# pi_breakout.net
KiCad netlist of a schematic drawn in Altium Designer
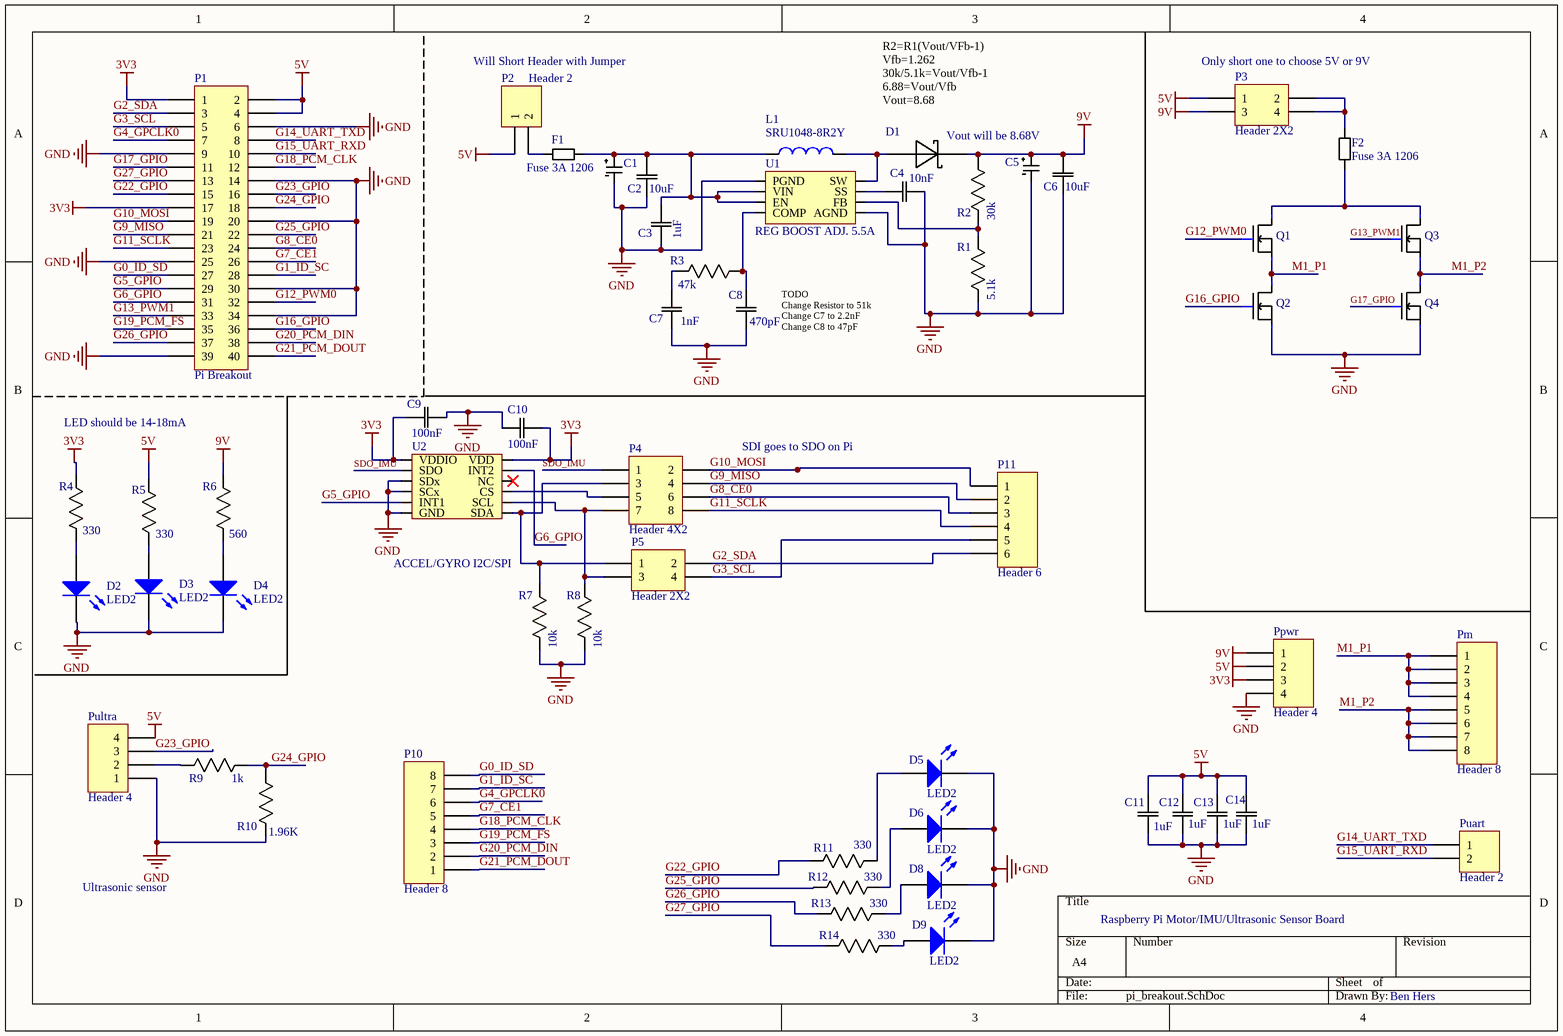
[diagram p0: pi_breakout.SchDoc]

(export (version "E")
  (design (tool "Eeschema 10.0.6"))
  (components
    (comp (ref "C1")
      (value "CAP ALUM 470UF RADIAL")
      (footprint "Aluminum Electrolytic Capacitors Radial")
      (description "470µF 35V Aluminum Electrolytic Capacitors Radial, Can - SMD  5000 Hrs @ 105°C")
      (fields (field (name "MF") "Panasonic Electronic Components") (field (name "MP") "EEV-FK1V471Q"))
      (libsource (lib "AltiumLibraries") (part "CAP ALUM 470UF Aluminum Electrolytic Radial"))
    )
    (comp (ref "C2")
      (value "10uF")
      (footprint "0805")
      (description "CAP CER 10UF 10V X5R 0805")
      (fields (field (name "MP") "C0805C106K8PACTU") (field (name "MF") "KEMET"))
      (libsource (lib "") (part "CAP 10uF 0805_1"))
    )
    (comp (ref "C3")
      (value "1uF")
      (footprint "0805")
      (description "CAP CER 1UF 50V X7R 0805")
      (fields (field (name "MP") "CL21B105KBFNNNE") (field (name "MF") "Samsung Electro-Mechanics"))
      (libsource (lib "") (part "CAP 1uF 0805_1"))
    )
    (comp (ref "C4")
      (value "10nF")
      (footprint "0805")
      (description "CAP CER 10000PF 50V X7R 0805")
      (fields (field (name "MP") "CC0805KRX7R9BB103") (field (name "MF") "Yageo"))
      (libsource (lib "AltiumLibraries") (part "CAP 10nF 0805"))
    )
    (comp (ref "C5")
      (value "CAP ALUM 470UF RADIAL")
      (footprint "Aluminum Electrolytic Capacitors Radial")
      (description "470µF 35V Aluminum Electrolytic Capacitors Radial, Can - SMD  5000 Hrs @ 105°C")
      (fields (field (name "MF") "Panasonic Electronic Components") (field (name "MP") "EEV-FK1V471Q"))
      (libsource (lib "AltiumLibraries") (part "CAP ALUM 470UF Aluminum Electrolytic Radial"))
    )
    (comp (ref "C6")
      (value "10uF")
      (footprint "0805")
      (description "CAP CER 10UF 10V X5R 0805")
      (fields (field (name "MP") "C0805C106K8PACTU") (field (name "MF") "KEMET"))
      (libsource (lib "AltiumLibraries") (part "CAP 10uF 0805"))
    )
    (comp (ref "C7")
      (value "1nF")
      (footprint "0805")
      (description "CAP CER 1000PF 50V X7R 0805")
      (fields (field (name "MP") "CC0805KRX7R9BB102") (field (name "MF") "Yageo"))
      (libsource (lib "AltiumLibraries") (part "CAP 1nF 0805"))
    )
    (comp (ref "C8")
      (value "470pF")
      (footprint "0805")
      (description "CAP CER 470PF 50V C0G/NPO 0805")
      (fields (field (name "MP") "CC0805JRNPO9BN471") (field (name "MF") "Yageo"))
      (libsource (lib "AltiumLibraries") (part "CAP 470pF 0805"))
    )
    (comp (ref "C9")
      (value "100nF")
      (footprint "0805")
      (description "CAP CER 0.1UF 50V X7R 0805")
      (fields (field (name "MP") "CC0805KRX7R9BB104") (field (name "MF") "Yageo"))
      (libsource (lib "AltiumLibraries") (part "CAP 100nF 0805"))
    )
    (comp (ref "C10")
      (value "100nF")
      (footprint "0805")
      (description "CAP CER 0.1UF 50V X7R 0805")
      (fields (field (name "MP") "CC0805KRX7R9BB104") (field (name "MF") "Yageo"))
      (libsource (lib "AltiumLibraries") (part "CAP 100nF 0805"))
    )
    (comp (ref "C11")
      (value "1uF")
      (footprint "0805")
      (description "CAP CER 1UF 50V X7R 0805")
      (fields (field (name "MP") "CL21B105KBFNNNE") (field (name "MF") "Samsung Electro-Mechanics"))
      (libsource (lib "AltiumLibraries") (part "CAP 1uF 0805"))
    )
    (comp (ref "C12")
      (value "1uF")
      (footprint "0805")
      (description "CAP CER 1UF 50V X7R 0805")
      (fields (field (name "MP") "CL21B105KBFNNNE") (field (name "MF") "Samsung Electro-Mechanics"))
      (libsource (lib "AltiumLibraries") (part "CAP 1uF 0805"))
    )
    (comp (ref "C13")
      (value "1uF")
      (footprint "0805")
      (description "CAP CER 1UF 50V X7R 0805")
      (fields (field (name "MP") "CL21B105KBFNNNE") (field (name "MF") "Samsung Electro-Mechanics"))
      (libsource (lib "AltiumLibraries") (part "CAP 1uF 0805"))
    )
    (comp (ref "C14")
      (value "1uF")
      (footprint "0805")
      (description "CAP CER 1UF 50V X7R 0805")
      (fields (field (name "MP") "CL21B105KBFNNNE") (field (name "MF") "Samsung Electro-Mechanics"))
      (libsource (lib "AltiumLibraries") (part "CAP 1uF 0805"))
    )
    (comp (ref "D1")
      (value "DIODE SCHOTTKY 40V 3A SMC")
      (footprint "SMC")
      (description "Diode Schottky 40V 3A Surface Mount SMC")
      (fields (field (name "MF") "Diodes Incorporated") (field (name "MP") "B340-13-F"))
      (libsource (lib "AltiumLibraries") (part "B340-13-F"))
    )
    (comp (ref "D2")
      (value "LED2")
      (footprint "3.2X1.6X1.1")
      (description "Typical RED, GREEN, YELLOW, AMBER GaAs LED")
      (fields (field (name "MF") "Lite-On Inc.") (field (name "MP") "LTST-C191KGKT"))
      (libsource (lib "AltiumLibraries") (part "LED GREEN SMD"))
    )
    (comp (ref "D3")
      (value "LED2")
      (footprint "3.2X1.6X1.1")
      (description "Typical RED, GREEN, YELLOW, AMBER GaAs LED")
      (fields (field (name "MF") "Lite-On Inc.") (field (name "MP") "LTST-C191KGKT"))
      (libsource (lib "AltiumLibraries") (part "LED GREEN SMD"))
    )
    (comp (ref "D4")
      (value "LED2")
      (footprint "3.2X1.6X1.1")
      (description "Typical RED, GREEN, YELLOW, AMBER GaAs LED")
      (fields (field (name "MF") "Lite-On Inc.") (field (name "MP") "LTST-C191KGKT"))
      (libsource (lib "AltiumLibraries") (part "LED GREEN SMD"))
    )
    (comp (ref "D5")
      (value "LED2")
      (footprint "3.2X1.6X1.1")
      (description "Typical RED, GREEN, YELLOW, AMBER GaAs LED")
      (fields (field (name "MF") "Lite-On Inc.") (field (name "MP") "LTST-C191KGKT"))
      (libsource (lib "AltiumLibraries") (part "LED GREEN SMD"))
    )
    (comp (ref "D6")
      (value "LED2")
      (footprint "3.2X1.6X1.1")
      (description "Typical RED, GREEN, YELLOW, AMBER GaAs LED")
      (fields (field (name "MF") "Lite-On Inc.") (field (name "MP") "LTST-C191KGKT"))
      (libsource (lib "AltiumLibraries") (part "LED GREEN SMD"))
    )
    (comp (ref "D8")
      (value "LED2")
      (footprint "3.2X1.6X1.1")
      (description "Typical RED, GREEN, YELLOW, AMBER GaAs LED")
      (fields (field (name "MF") "Lite-On Inc.") (field (name "MP") "LTST-C191KGKT"))
      (libsource (lib "AltiumLibraries") (part "LED GREEN SMD"))
    )
    (comp (ref "D9")
      (value "LED2")
      (footprint "3.2X1.6X1.1")
      (description "Typical RED, GREEN, YELLOW, AMBER GaAs LED")
      (fields (field (name "MF") "Lite-On Inc.") (field (name "MP") "LTST-C191KGKT"))
      (libsource (lib "AltiumLibraries") (part "LED GREEN SMD"))
    )
    (comp (ref "F1")
      (value "Fuse 3A 1206")
      (footprint "1206")
      (description "FUSE 3.0A 63VAC/DC SLOW 1206")
      (fields (field (name "MF") "Bel Fuse Inc.") (field (name "MP") "0685T3000-01"))
      (libsource (lib "AltiumLibraries") (part "Fuse 3A 1206"))
    )
    (comp (ref "F2")
      (value "Fuse 3A 1206")
      (footprint "1206")
      (description "FUSE 3.0A 63VAC/DC SLOW 1206")
      (fields (field (name "MF") "Bel Fuse Inc.") (field (name "MP") "0685T3000-01"))
      (libsource (lib "AltiumLibraries") (part "Fuse 3A 1206"))
    )
    (comp (ref "L1")
      (value "SRU1048-8R2Y")
      (footprint "Inductor")
      (description "FIXED IND 8.2UH 4.6A 15 MOHM SMD")
      (fields (field (name "MF") "Bourns Inc."))
      (libsource (lib "AltiumLibraries") (part "SRU1048-8R2Y"))
    )
    (comp (ref "P1")
      (value "Pi Breakout")
      (footprint "HDR2X20")
      (description "Header, 20-Pin, Dual row")
      (fields (field (name "PUBLISHER") "Altium Limited"))
      (libsource (lib "Miscellaneous Connectors") (part "Header 20X2"))
    )
    (comp (ref "P2")
      (value "Header 2")
      (footprint "HDR1X2")
      (description "Header, 2-Pin")
      (fields (field (name "PUBLISHER") "Altium Limited"))
      (libsource (lib "Miscellaneous Connectors") (part "Header 2"))
    )
    (comp (ref "P3")
      (value "Header 2X2")
      (footprint "HDR2X2")
      (description "Header, 2-Pin, Dual row")
      (fields (field (name "PUBLISHER") "Altium Limited"))
      (libsource (lib "Miscellaneous Connectors") (part "Header 2X2"))
    )
    (comp (ref "P4")
      (value "Header 4X2")
      (footprint "HDR2X4")
      (description "Header, 4-Pin, Dual row")
      (fields (field (name "PUBLISHER") "Altium Limited"))
      (libsource (lib "Miscellaneous Connectors") (part "Header 4X2"))
    )
    (comp (ref "P5")
      (value "Header 2X2")
      (footprint "HDR2X2")
      (description "Header, 2-Pin, Dual row")
      (fields (field (name "PUBLISHER") "Altium Limited"))
      (libsource (lib "Miscellaneous Connectors") (part "Header 2X2"))
    )
    (comp (ref "P10")
      (value "Header 8")
      (footprint "HDR1X8")
      (description "Header, 8-Pin")
      (fields (field (name "PUBLISHER") "Altium Limited"))
      (libsource (lib "Miscellaneous Connectors") (part "Header 8"))
    )
    (comp (ref "P11")
      (value "Header 6")
      (footprint "HDR1X6")
      (description "Header, 6-Pin")
      (fields (field (name "PUBLISHER") "Altium Limited"))
      (libsource (lib "Miscellaneous Connectors") (part "Header 6"))
    )
    (comp (ref "Pm")
      (value "Header 8")
      (footprint "HDR1X8")
      (description "Header, 8-Pin")
      (fields (field (name "PUBLISHER") "Altium Limited"))
      (libsource (lib "") (part "Header 8_1"))
    )
    (comp (ref "Ppwr")
      (value "Header 4")
      (footprint "HDR1X4")
      (description "Header, 4-Pin")
      (fields (field (name "PUBLISHER") "Altium Limited"))
      (libsource (lib "") (part "Header 4_1"))
    )
    (comp (ref "Puart")
      (value "Header 2")
      (footprint "HDR1X2")
      (description "Header, 2-Pin")
      (fields (field (name "PUBLISHER") "Altium Limited"))
      (libsource (lib "") (part "Header 2_1"))
    )
    (comp (ref "Pultra")
      (value "Header 4")
      (footprint "HDR1X4")
      (description "Header, 4-Pin")
      (fields (field (name "PUBLISHER") "Altium Limited"))
      (libsource (lib "Miscellaneous Connectors") (part "Header 4"))
    )
    (comp (ref "Q1")
      (value "N-Channel")
      (footprint "8-SOIC MOSFET")
      (description "MOSFET N-CH 30V 18.5A 8-SOIC")
      (fields (field (name "MF") "ON Semiconductor") (field (name "MP") "FDS8813NZ"))
      (libsource (lib "AltiumLibraries") (part "MOSFET N Channel 8-SOIC"))
    )
    (comp (ref "Q2")
      (value "N-Channel")
      (footprint "8-SOIC MOSFET")
      (description "MOSFET N-CH 30V 18.5A 8-SOIC")
      (fields (field (name "MF") "ON Semiconductor") (field (name "MP") "FDS8813NZ"))
      (libsource (lib "AltiumLibraries") (part "MOSFET N Channel 8-SOIC"))
    )
    (comp (ref "Q3")
      (value "N-Channel")
      (footprint "8-SOIC MOSFET")
      (description "MOSFET N-CH 30V 18.5A 8-SOIC")
      (fields (field (name "MF") "ON Semiconductor") (field (name "MP") "FDS8813NZ"))
      (libsource (lib "AltiumLibraries") (part "MOSFET N Channel 8-SOIC"))
    )
    (comp (ref "Q4")
      (value "N-Channel")
      (footprint "8-SOIC MOSFET")
      (description "MOSFET N-CH 30V 18.5A 8-SOIC")
      (fields (field (name "MF") "ON Semiconductor") (field (name "MP") "FDS8813NZ"))
      (libsource (lib "AltiumLibraries") (part "MOSFET N Channel 8-SOIC"))
    )
    (comp (ref "R1")
      (value "5.1k")
      (footprint "0805")
      (description "RES SMD 5.1K OHM 1% 1/8W 0805")
      (fields (field (name "MP") "RC0805FR-075K1L") (field (name "MF") "Yageo"))
      (libsource (lib "AltiumLibraries") (part "RES 5.1k 0805"))
    )
    (comp (ref "R2")
      (value "30k")
      (footprint "0805")
      (description "RES SMD 30K OHM 1% 1/8W 0805")
      (fields (field (name "MP") "RC0805FR-0730KL") (field (name "MF") "Yageo"))
      (libsource (lib "AltiumLibraries") (part "RES 30k 0805"))
    )
    (comp (ref "R3")
      (value "47k")
      (footprint "0805")
      (description "RES SMD 47K OHM 1% 1/8W 0805")
      (fields (field (name "MP") "RC0805FR-0747KL") (field (name "MF") "Yageo"))
      (libsource (lib "AltiumLibraries") (part "RES 47k 0805"))
    )
    (comp (ref "R4")
      (value "330")
      (footprint "0805")
      (description "RES SMD 330 OHM 1% 1/8W 0805")
      (fields (field (name "MP") "RC0805FR-07330RL") (field (name "MF") "Yageo"))
      (libsource (lib "AltiumLibraries") (part "RES 330 0805"))
    )
    (comp (ref "R5")
      (value "330")
      (footprint "0805")
      (description "RES SMD 330 OHM 1% 1/8W 0805")
      (fields (field (name "MP") "RC0805FR-07330RL") (field (name "MF") "Yageo"))
      (libsource (lib "AltiumLibraries") (part "RES 330 0805"))
    )
    (comp (ref "R6")
      (value "560")
      (footprint "0805")
      (description "RES 560 OHM 1% 1/8W 0805")
      (fields (field (name "MP") "RMCF0805FT560R") (field (name "MF") "Stackpole Electronics Inc"))
      (libsource (lib "AltiumLibraries") (part "RES 560 0805"))
    )
    (comp (ref "R7")
      (value "10k")
      (footprint "0805")
      (description "RES SMD 10K OHM 1% 1/8W 0805")
      (fields (field (name "MP") "RC0805FR-0710KL") (field (name "MF") "Yageo"))
      (libsource (lib "AltiumLibraries") (part "RES 10k 0805"))
    )
    (comp (ref "R8")
      (value "10k")
      (footprint "0805")
      (description "RES SMD 10K OHM 1% 1/8W 0805")
      (fields (field (name "MP") "RC0805FR-0710KL") (field (name "MF") "Yageo"))
      (libsource (lib "AltiumLibraries") (part "RES 10k 0805"))
    )
    (comp (ref "R9")
      (value "1k")
      (footprint "0805")
      (description "RES SMD 1K OHM 5% 1/8W 0805")
      (fields (field (name "MP") "RC0805JR-071KL") (field (name "MF") "Yageo"))
      (libsource (lib "AltiumLibraries") (part "RES 1k 0805"))
    )
    (comp (ref "R10")
      (value "1.96K")
      (footprint "0805")
      (description "RES SMD 1.96K OHM 1% 1/8W 0805")
      (fields (field (name "MP") "ERJ-6ENF1961V") (field (name "MF") "Panasonic Electronic Components"))
      (libsource (lib "AltiumLibraries") (part "RES 1.96k 0805"))
    )
    (comp (ref "R11")
      (value "330")
      (footprint "0805")
      (description "RES SMD 330 OHM 1% 1/8W 0805")
      (fields (field (name "MP") "RC0805FR-07330RL") (field (name "MF") "Yageo"))
      (libsource (lib "AltiumLibraries") (part "RES 330 0805"))
    )
    (comp (ref "R12")
      (value "330")
      (footprint "0805")
      (description "RES SMD 330 OHM 1% 1/8W 0805")
      (fields (field (name "MP") "RC0805FR-07330RL") (field (name "MF") "Yageo"))
      (libsource (lib "AltiumLibraries") (part "RES 330 0805"))
    )
    (comp (ref "R13")
      (value "330")
      (footprint "0805")
      (description "RES SMD 330 OHM 1% 1/8W 0805")
      (fields (field (name "MP") "RC0805FR-07330RL") (field (name "MF") "Yageo"))
      (libsource (lib "AltiumLibraries") (part "RES 330 0805"))
    )
    (comp (ref "R14")
      (value "330")
      (footprint "0805")
      (description "RES SMD 330 OHM 1% 1/8W 0805")
      (fields (field (name "MP") "RC0805FR-07330RL") (field (name "MF") "Yageo"))
      (libsource (lib "AltiumLibraries") (part "RES 330 0805"))
    )
    (comp (ref "U1")
      (value "REG BOOST ADJ. 5.5A")
      (footprint "ICREGBOOSTADJUSTABLE5.5A8SO")
      (fields (field (name "MF") "Diodes Incorporated") (field (name "MP") "PAM2423AECADJR"))
      (libsource (lib "AltiumLibraries") (part "REG BOOST ADJUSTABLE 5.5A 8SO"))
    )
    (comp (ref "U2")
      (value "ACCEL/GYRO I2C/SPI")
      (footprint "IMU 14-LGA")
      (description "Accelerometer, Gyroscope, Temperature, 6 Axis Sensor I²C, SPI Output")
      (fields (field (name "MP") "LSM6DSLTR") (field (name "MF") "STMicroelectronics"))
      (libsource (lib "AltiumLibraries") (part "IMU 14LGA"))
    )
  )
  (nets
    (net (code "1") (name "/G0_ID_SD") (class "Default")
      (node (ref "P1") (pin "27") (pinfunction "27_27") (pintype "passive"))
      (node (ref "P10") (pin "8") (pinfunction "8_8") (pintype "passive"))
    )
    (net (code "2") (name "/G1_ID_SC") (class "Default")
      (node (ref "P1") (pin "28") (pinfunction "28_28") (pintype "passive"))
      (node (ref "P10") (pin "7") (pinfunction "7_7") (pintype "passive"))
    )
    (net (code "3") (name "/G2_SDA") (class "Default")
      (node (ref "P1") (pin "3") (pinfunction "3_3") (pintype "passive"))
      (node (ref "P11") (pin "6") (pinfunction "6_6") (pintype "passive"))
      (node (ref "P5") (pin "2") (pinfunction "2_2") (pintype "passive"))
    )
    (net (code "4") (name "/G3_SCL") (class "Default")
      (node (ref "P1") (pin "5") (pinfunction "5_5") (pintype "passive"))
      (node (ref "P11") (pin "5") (pinfunction "5_5") (pintype "passive"))
      (node (ref "P5") (pin "4") (pinfunction "4_4") (pintype "passive"))
    )
    (net (code "5") (name "/G4_GPCLK0") (class "Default")
      (node (ref "P1") (pin "7") (pinfunction "7_7") (pintype "passive"))
      (node (ref "P10") (pin "6") (pinfunction "6_6") (pintype "passive"))
    )
    (net (code "6") (name "/G5_GPIO") (class "Default")
      (node (ref "P1") (pin "29") (pinfunction "29_29") (pintype "passive"))
      (node (ref "U2") (pin "INT1") (pinfunction "INT1_INT1") (pintype "passive"))
    )
    (net (code "7") (name "/G6_GPIO") (class "Default")
      (node (ref "P1") (pin "31") (pinfunction "31_31") (pintype "passive"))
      (node (ref "U2") (pin "INT2") (pinfunction "INT2_INT2") (pintype "passive"))
    )
    (net (code "8") (name "/G7_CE1") (class "Default")
      (node (ref "P1") (pin "26") (pinfunction "26_26") (pintype "passive"))
      (node (ref "P10") (pin "5") (pinfunction "5_5") (pintype "passive"))
    )
    (net (code "9") (name "/G8_CE0") (class "Default")
      (node (ref "P1") (pin "24") (pinfunction "24_24") (pintype "passive"))
      (node (ref "P11") (pin "3") (pinfunction "3_3") (pintype "passive"))
      (node (ref "P4") (pin "6") (pinfunction "6_6") (pintype "passive"))
    )
    (net (code "10") (name "/G9_MISO") (class "Default")
      (node (ref "P1") (pin "21") (pinfunction "21_21") (pintype "passive"))
      (node (ref "P11") (pin "2") (pinfunction "2_2") (pintype "passive"))
      (node (ref "P4") (pin "4") (pinfunction "4_4") (pintype "passive"))
    )
    (net (code "11") (name "/G10_MOSI") (class "Default")
      (node (ref "P1") (pin "19") (pinfunction "19_19") (pintype "passive"))
      (node (ref "P11") (pin "1") (pinfunction "1_1") (pintype "passive"))
      (node (ref "P4") (pin "2") (pinfunction "2_2") (pintype "passive"))
    )
    (net (code "12") (name "/G11_SCLK") (class "Default")
      (node (ref "P1") (pin "23") (pinfunction "23_23") (pintype "passive"))
      (node (ref "P11") (pin "4") (pinfunction "4_4") (pintype "passive"))
      (node (ref "P4") (pin "8") (pinfunction "8_8") (pintype "passive"))
    )
    (net (code "13") (name "/G12_PWM0") (class "Default")
      (node (ref "P1") (pin "32") (pinfunction "32_32") (pintype "passive"))
      (node (ref "Q1") (pin "G") (pinfunction "G_G") (pintype "passive"))
    )
    (net (code "14") (name "/G13_PWM1") (class "Default")
      (node (ref "P1") (pin "33") (pinfunction "33_33") (pintype "passive"))
      (node (ref "Q3") (pin "G") (pinfunction "G_G") (pintype "passive"))
    )
    (net (code "15") (name "/G14_UART_TXD") (class "Default")
      (node (ref "P1") (pin "8") (pinfunction "8_8") (pintype "passive"))
      (node (ref "Puart") (pin "1") (pinfunction "1_1") (pintype "passive"))
    )
    (net (code "16") (name "/G15_UART_RXD") (class "Default")
      (node (ref "P1") (pin "10") (pinfunction "10_10") (pintype "passive"))
      (node (ref "Puart") (pin "2") (pinfunction "2_2") (pintype "passive"))
    )
    (net (code "17") (name "/G16_GPIO") (class "Default")
      (node (ref "P1") (pin "36") (pinfunction "36_36") (pintype "passive"))
      (node (ref "Q2") (pin "G") (pinfunction "G_G") (pintype "passive"))
    )
    (net (code "18") (name "/G17_GPIO") (class "Default")
      (node (ref "P1") (pin "11") (pinfunction "11_11") (pintype "passive"))
      (node (ref "Q4") (pin "G") (pinfunction "G_G") (pintype "passive"))
    )
    (net (code "19") (name "/G18_PCM_CLK") (class "Default")
      (node (ref "P1") (pin "12") (pinfunction "12_12") (pintype "passive"))
      (node (ref "P10") (pin "4") (pinfunction "4_4") (pintype "passive"))
    )
    (net (code "20") (name "/G19_PCM_FS") (class "Default")
      (node (ref "P1") (pin "35") (pinfunction "35_35") (pintype "passive"))
      (node (ref "P10") (pin "3") (pinfunction "3_3") (pintype "passive"))
    )
    (net (code "21") (name "/G20_PCM_DIN") (class "Default")
      (node (ref "P1") (pin "38") (pinfunction "38_38") (pintype "passive"))
      (node (ref "P10") (pin "2") (pinfunction "2_2") (pintype "passive"))
    )
    (net (code "22") (name "/G21_PCM_DOUT") (class "Default")
      (node (ref "P1") (pin "40") (pinfunction "40_40") (pintype "passive"))
      (node (ref "P10") (pin "1") (pinfunction "1_1") (pintype "passive"))
    )
    (net (code "23") (name "/G22_GPIO") (class "Default")
      (node (ref "P1") (pin "15") (pinfunction "15_15") (pintype "passive"))
      (node (ref "R11") (pin "1") (pinfunction "R1_1") (pintype "passive"))
    )
    (net (code "24") (name "/G23_GPIO") (class "Default")
      (node (ref "P1") (pin "16") (pinfunction "16_16") (pintype "passive"))
      (node (ref "Pultra") (pin "3") (pinfunction "3_3") (pintype "passive"))
    )
    (net (code "25") (name "/G24_GPIO") (class "Default")
      (node (ref "P1") (pin "18") (pinfunction "18_18") (pintype "passive"))
      (node (ref "R10") (pin "1") (pinfunction "R1_1") (pintype "passive"))
      (node (ref "R9") (pin "1") (pinfunction "R1_1") (pintype "passive"))
    )
    (net (code "26") (name "/G25_GPIO") (class "Default")
      (node (ref "P1") (pin "22") (pinfunction "22_22") (pintype "passive"))
      (node (ref "R12") (pin "1") (pinfunction "R1_1") (pintype "passive"))
    )
    (net (code "27") (name "/G26_GPIO") (class "Default")
      (node (ref "P1") (pin "37") (pinfunction "37_37") (pintype "passive"))
      (node (ref "R13") (pin "1") (pinfunction "R1_1") (pintype "passive"))
    )
    (net (code "28") (name "/G27_GPIO") (class "Default")
      (node (ref "P1") (pin "13") (pinfunction "13_13") (pintype "passive"))
      (node (ref "R14") (pin "1") (pinfunction "R1_1") (pintype "passive"))
    )
    (net (code "29") (name "/M1_P1") (class "Default")
      (node (ref "Pm") (pin "1") (pinfunction "1_1") (pintype "passive"))
      (node (ref "Pm") (pin "2") (pinfunction "2_2") (pintype "passive"))
      (node (ref "Pm") (pin "3") (pinfunction "3_3") (pintype "passive"))
      (node (ref "Pm") (pin "4") (pinfunction "4_4") (pintype "passive"))
      (node (ref "Q1") (pin "S") (pinfunction "S_S") (pintype "passive"))
      (node (ref "Q2") (pin "D") (pinfunction "D_D") (pintype "passive"))
    )
    (net (code "30") (name "/M1_P2") (class "Default")
      (node (ref "Pm") (pin "5") (pinfunction "5_5") (pintype "passive"))
      (node (ref "Pm") (pin "6") (pinfunction "6_6") (pintype "passive"))
      (node (ref "Pm") (pin "7") (pinfunction "7_7") (pintype "passive"))
      (node (ref "Pm") (pin "8") (pinfunction "8_8") (pintype "passive"))
      (node (ref "Q3") (pin "S") (pinfunction "S_S") (pintype "passive"))
      (node (ref "Q4") (pin "D") (pinfunction "D_D") (pintype "passive"))
    )
    (net (code "31") (name "/SDO_IMU") (class "Default")
      (node (ref "P4") (pin "1") (pinfunction "1_1") (pintype "passive"))
      (node (ref "U2") (pin "SDO") (pinfunction "SDO_SDO") (pintype "passive"))
    )
    (net (code "32") (name "3V3") (class "Default")
      (node (ref "C10") (pin "2") (pinfunction "C2_2") (pintype "passive"))
      (node (ref "C9") (pin "1") (pinfunction "C1_1") (pintype "passive"))
      (node (ref "P1") (pin "1") (pinfunction "1_1") (pintype "passive"))
      (node (ref "P1") (pin "17") (pinfunction "17_17") (pintype "passive"))
      (node (ref "Ppwr") (pin "3") (pinfunction "3_3") (pintype "passive"))
      (node (ref "R4") (pin "1") (pinfunction "R1_1") (pintype "passive"))
      (node (ref "U2") (pin "VDD") (pinfunction "VDD_VDD") (pintype "passive"))
      (node (ref "U2") (pin "VDDIO") (pinfunction "VDDIO_VDDIO") (pintype "passive"))
    )
    (net (code "33") (name "5V") (class "Default")
      (node (ref "C11") (pin "2") (pinfunction "C2_2") (pintype "passive"))
      (node (ref "C12") (pin "2") (pinfunction "C2_2") (pintype "passive"))
      (node (ref "C13") (pin "2") (pinfunction "C2_2") (pintype "passive"))
      (node (ref "C14") (pin "2") (pinfunction "C2_2") (pintype "passive"))
      (node (ref "P1") (pin "2") (pinfunction "2_2") (pintype "passive"))
      (node (ref "P1") (pin "4") (pinfunction "4_4") (pintype "passive"))
      (node (ref "P2") (pin "1") (pinfunction "1_1") (pintype "passive"))
      (node (ref "P3") (pin "1") (pinfunction "1_1") (pintype "passive"))
      (node (ref "Ppwr") (pin "2") (pinfunction "2_2") (pintype "passive"))
      (node (ref "Pultra") (pin "4") (pinfunction "4_4") (pintype "passive"))
      (node (ref "R5") (pin "1") (pinfunction "R1_1") (pintype "passive"))
    )
    (net (code "34") (name "9V") (class "Default")
      (node (ref "C5") (pin "1") (pinfunction "1_1") (pintype "passive"))
      (node (ref "C6") (pin "2") (pinfunction "C2_2") (pintype "passive"))
      (node (ref "D1") (pin "1") (pinfunction "K_1") (pintype "passive"))
      (node (ref "P3") (pin "3") (pinfunction "3_3") (pintype "passive"))
      (node (ref "Ppwr") (pin "1") (pinfunction "1_1") (pintype "passive"))
      (node (ref "R2") (pin "1") (pinfunction "R1_1") (pintype "passive"))
      (node (ref "R6") (pin "1") (pinfunction "R1_1") (pintype "passive"))
    )
    (net (code "35") (name "GND") (class "Default")
      (node (ref "C1") (pin "2") (pinfunction "2_2") (pintype "passive"))
      (node (ref "C10") (pin "1") (pinfunction "C1_1") (pintype "passive"))
      (node (ref "C11") (pin "1") (pinfunction "C1_1") (pintype "passive"))
      (node (ref "C12") (pin "1") (pinfunction "C1_1") (pintype "passive"))
      (node (ref "C13") (pin "1") (pinfunction "C1_1") (pintype "passive"))
      (node (ref "C14") (pin "1") (pinfunction "C1_1") (pintype "passive"))
      (node (ref "C2") (pin "1") (pinfunction "C1_1") (pintype "passive"))
      (node (ref "C3") (pin "1") (pinfunction "C1_1") (pintype "passive"))
      (node (ref "C4") (pin "2") (pinfunction "C2_2") (pintype "passive"))
      (node (ref "C5") (pin "2") (pinfunction "2_2") (pintype "passive"))
      (node (ref "C6") (pin "1") (pinfunction "C1_1") (pintype "passive"))
      (node (ref "C7") (pin "1") (pinfunction "C1_1") (pintype "passive"))
      (node (ref "C8") (pin "1") (pinfunction "C1_1") (pintype "passive"))
      (node (ref "C9") (pin "2") (pinfunction "C2_2") (pintype "passive"))
      (node (ref "D2") (pin "2") (pinfunction "K_2") (pintype "passive"))
      (node (ref "D3") (pin "2") (pinfunction "K_2") (pintype "passive"))
      (node (ref "D4") (pin "2") (pinfunction "K_2") (pintype "passive"))
      (node (ref "D5") (pin "2") (pinfunction "K_2") (pintype "passive"))
      (node (ref "D6") (pin "2") (pinfunction "K_2") (pintype "passive"))
      (node (ref "D8") (pin "2") (pinfunction "K_2") (pintype "passive"))
      (node (ref "D9") (pin "2") (pinfunction "K_2") (pintype "passive"))
      (node (ref "P1") (pin "14") (pinfunction "14_14") (pintype "passive"))
      (node (ref "P1") (pin "20") (pinfunction "20_20") (pintype "passive"))
      (node (ref "P1") (pin "25") (pinfunction "25_25") (pintype "passive"))
      (node (ref "P1") (pin "30") (pinfunction "30_30") (pintype "passive"))
      (node (ref "P1") (pin "34") (pinfunction "34_34") (pintype "passive"))
      (node (ref "P1") (pin "39") (pinfunction "39_39") (pintype "passive"))
      (node (ref "P1") (pin "6") (pinfunction "6_6") (pintype "passive"))
      (node (ref "P1") (pin "9") (pinfunction "9_9") (pintype "passive"))
      (node (ref "Ppwr") (pin "4") (pinfunction "4_4") (pintype "passive"))
      (node (ref "Pultra") (pin "1") (pinfunction "1_1") (pintype "passive"))
      (node (ref "Q2") (pin "S") (pinfunction "S_S") (pintype "passive"))
      (node (ref "Q4") (pin "S") (pinfunction "S_S") (pintype "passive"))
      (node (ref "R1") (pin "2") (pinfunction "R2_2") (pintype "passive"))
      (node (ref "R10") (pin "2") (pinfunction "R2_2") (pintype "passive"))
      (node (ref "R7") (pin "2") (pinfunction "R2_2") (pintype "passive"))
      (node (ref "R8") (pin "2") (pinfunction "R2_2") (pintype "passive"))
      (node (ref "U1") (pin "AGND") (pinfunction "AGND_AGND") (pintype "passive"))
      (node (ref "U1") (pin "PGND") (pinfunction "PGND_PGND") (pintype "passive"))
      (node (ref "U2") (pin "GND") (pinfunction "GND_GND") (pintype "passive"))
      (node (ref "U2") (pin "SCx") (pinfunction "SCx_SCx") (pintype "passive"))
      (node (ref "U2") (pin "SDx") (pinfunction "SDx_SDx") (pintype "passive"))
    )
    (net (code "36") (name "Net-(C2-C2)") (class "Default")
      (node (ref "C1") (pin "1") (pinfunction "1_1") (pintype "passive"))
      (node (ref "C2") (pin "2") (pinfunction "C2_2") (pintype "passive"))
      (node (ref "C3") (pin "2") (pinfunction "C2_2") (pintype "passive"))
      (node (ref "F1") (pin "2") (pinfunction "2_2") (pintype "passive"))
      (node (ref "L1") (pin "1") (pinfunction "1_1") (pintype "passive"))
      (node (ref "U1") (pin "EN") (pinfunction "EN_EN") (pintype "passive"))
      (node (ref "U1") (pin "VIN") (pinfunction "VIN_VIN") (pintype "passive"))
    )
    (net (code "37") (name "Net-(C4-C1)") (class "Default")
      (node (ref "C4") (pin "1") (pinfunction "C1_1") (pintype "passive"))
      (node (ref "U1") (pin "SS") (pinfunction "SS_SS") (pintype "passive"))
    )
    (net (code "38") (name "Net-(C7-C2)") (class "Default")
      (node (ref "C7") (pin "2") (pinfunction "C2_2") (pintype "passive"))
      (node (ref "R3") (pin "2") (pinfunction "R2_2") (pintype "passive"))
    )
    (net (code "39") (name "Net-(C8-C2)") (class "Default")
      (node (ref "C8") (pin "2") (pinfunction "C2_2") (pintype "passive"))
      (node (ref "R3") (pin "1") (pinfunction "R1_1") (pintype "passive"))
      (node (ref "U1") (pin "COMP") (pinfunction "COMP_COMP") (pintype "passive"))
    )
    (net (code "40") (name "Net-(D1-A)") (class "Default")
      (node (ref "D1") (pin "2") (pinfunction "A_2") (pintype "passive"))
      (node (ref "L1") (pin "2") (pinfunction "2_2") (pintype "passive"))
      (node (ref "U1") (pin "SW") (pinfunction "SW_SW") (pintype "passive"))
    )
    (net (code "41") (name "Net-(D2-A)") (class "Default")
      (node (ref "D2") (pin "1") (pinfunction "A_1") (pintype "passive"))
      (node (ref "R4") (pin "2") (pinfunction "R2_2") (pintype "passive"))
    )
    (net (code "42") (name "Net-(D3-A)") (class "Default")
      (node (ref "D3") (pin "1") (pinfunction "A_1") (pintype "passive"))
      (node (ref "R5") (pin "2") (pinfunction "R2_2") (pintype "passive"))
    )
    (net (code "43") (name "Net-(D4-A)") (class "Default")
      (node (ref "D4") (pin "1") (pinfunction "A_1") (pintype "passive"))
      (node (ref "R6") (pin "2") (pinfunction "R2_2") (pintype "passive"))
    )
    (net (code "44") (name "Net-(D5-A)") (class "Default")
      (node (ref "D5") (pin "1") (pinfunction "A_1") (pintype "passive"))
      (node (ref "R11") (pin "2") (pinfunction "R2_2") (pintype "passive"))
    )
    (net (code "45") (name "Net-(D6-A)") (class "Default")
      (node (ref "D6") (pin "1") (pinfunction "A_1") (pintype "passive"))
      (node (ref "R12") (pin "2") (pinfunction "R2_2") (pintype "passive"))
    )
    (net (code "46") (name "Net-(D8-A)") (class "Default")
      (node (ref "D8") (pin "1") (pinfunction "A_1") (pintype "passive"))
      (node (ref "R13") (pin "2") (pinfunction "R2_2") (pintype "passive"))
    )
    (net (code "47") (name "Net-(D9-A)") (class "Default")
      (node (ref "D9") (pin "1") (pinfunction "A_1") (pintype "passive"))
      (node (ref "R14") (pin "2") (pinfunction "R2_2") (pintype "passive"))
    )
    (net (code "48") (name "Net-(F1-Pad1)") (class "Default")
      (node (ref "F1") (pin "1") (pinfunction "1_1") (pintype "passive"))
      (node (ref "P2") (pin "2") (pinfunction "2_2") (pintype "passive"))
    )
    (net (code "49") (name "Net-(F2-Pad1)") (class "Default")
      (node (ref "F2") (pin "1") (pinfunction "1_1") (pintype "passive"))
      (node (ref "Q1") (pin "D") (pinfunction "D_D") (pintype "passive"))
      (node (ref "Q3") (pin "D") (pinfunction "D_D") (pintype "passive"))
    )
    (net (code "50") (name "Net-(F2-Pad2)") (class "Default")
      (node (ref "F2") (pin "2") (pinfunction "2_2") (pintype "passive"))
      (node (ref "P3") (pin "2") (pinfunction "2_2") (pintype "passive"))
      (node (ref "P3") (pin "4") (pinfunction "4_4") (pintype "passive"))
    )
    (net (code "51") (name "Net-(P4-Pad5)") (class "Default")
      (node (ref "P4") (pin "5") (pinfunction "5_5") (pintype "passive"))
      (node (ref "U2") (pin "CS") (pinfunction "CS_CS") (pintype "passive"))
    )
    (net (code "52") (name "Net-(R1-R1)") (class "Default")
      (node (ref "R1") (pin "1") (pinfunction "R1_1") (pintype "passive"))
      (node (ref "R2") (pin "2") (pinfunction "R2_2") (pintype "passive"))
      (node (ref "U1") (pin "FB") (pinfunction "FB_FB") (pintype "passive"))
    )
    (net (code "53") (name "Net-(R7-R1)") (class "Default")
      (node (ref "P4") (pin "3") (pinfunction "3_3") (pintype "passive"))
      (node (ref "P5") (pin "1") (pinfunction "1_1") (pintype "passive"))
      (node (ref "R7") (pin "1") (pinfunction "R1_1") (pintype "passive"))
      (node (ref "U2") (pin "SDA") (pinfunction "SDA_SDA") (pintype "passive"))
    )
    (net (code "54") (name "Net-(R8-R1)") (class "Default")
      (node (ref "P4") (pin "7") (pinfunction "7_7") (pintype "passive"))
      (node (ref "P5") (pin "3") (pinfunction "3_3") (pintype "passive"))
      (node (ref "R8") (pin "1") (pinfunction "R1_1") (pintype "passive"))
      (node (ref "U2") (pin "SCL") (pinfunction "SCL_SCL") (pintype "passive"))
    )
    (net (code "55") (name "Net-(R9-R2)") (class "Default")
      (node (ref "Pultra") (pin "2") (pinfunction "2_2") (pintype "passive"))
      (node (ref "R9") (pin "2") (pinfunction "R2_2") (pintype "passive"))
    )
    (net (code "56") (name "unconnected-(U2-PadNC)") (class "Default")
      (node (ref "U2") (pin "NC") (pinfunction "NC_NC") (pintype "passive+no_connect"))
    )
  )
)
